# carte_moteurs_robotech.net
KiCad netlist of a schematic drawn in EAGLE
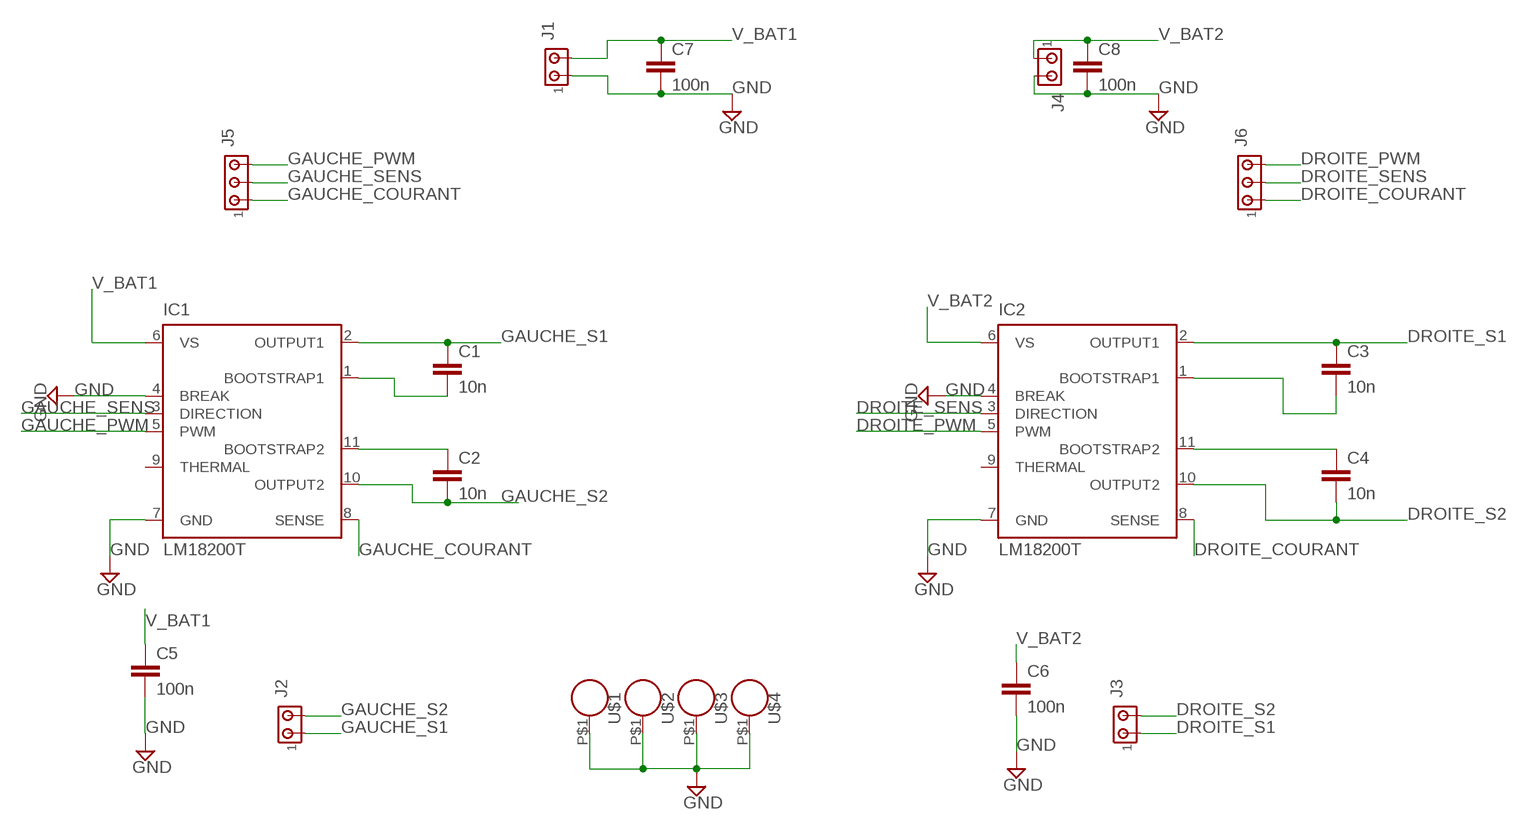
[diagram p0: schematic, sheet 1]

(export (version "E")
  (design (tool "Eeschema 10.0.6"))
  (components
    (comp (ref "C1")
      (value "10n")
      (footprint "eagle-import:C7.5B3")
      (libsource (lib "eagle-import") (part "C7.5/3"))
    )
    (comp (ref "C2")
      (value "10n")
      (footprint "eagle-import:C7.5B3")
      (libsource (lib "eagle-import") (part "C7.5/3"))
    )
    (comp (ref "C3")
      (value "10n")
      (footprint "eagle-import:C7.5B3")
      (libsource (lib "eagle-import") (part "C7.5/3"))
    )
    (comp (ref "C4")
      (value "10n")
      (footprint "eagle-import:C7.5B3")
      (libsource (lib "eagle-import") (part "C7.5/3"))
    )
    (comp (ref "C5")
      (value "100n")
      (footprint "eagle-import:C7.5B3")
      (libsource (lib "eagle-import") (part "C7.5/3"))
    )
    (comp (ref "C6")
      (value "100n")
      (footprint "eagle-import:C7.5B3")
      (libsource (lib "eagle-import") (part "C7.5/3"))
    )
    (comp (ref "C7")
      (value "100n")
      (footprint "eagle-import:C7.5B3")
      (libsource (lib "eagle-import") (part "C7.5/3"))
    )
    (comp (ref "C8")
      (value "100n")
      (footprint "eagle-import:C7.5B3")
      (libsource (lib "eagle-import") (part "C7.5/3"))
    )
    (comp (ref "IC1")
      (value "LM18200T")
      (footprint "eagle-import:TO-220-11")
      (libsource (lib "eagle-import") (part "LM18200T"))
    )
    (comp (ref "IC2")
      (value "LM18200T")
      (footprint "eagle-import:TO-220-11")
      (libsource (lib "eagle-import") (part "LM18200T"))
    )
    (comp (ref "J1")
      (value "MTA02-156")
      (footprint "eagle-import:1X2MTA")
      (libsource (lib "eagle-import") (part "MTA02-156"))
    )
    (comp (ref "J2")
      (value "MTA02-156")
      (footprint "eagle-import:1X2MTA")
      (libsource (lib "eagle-import") (part "MTA02-156"))
    )
    (comp (ref "J3")
      (value "MTA02-156")
      (footprint "eagle-import:1X2MTA")
      (libsource (lib "eagle-import") (part "MTA02-156"))
    )
    (comp (ref "J4")
      (value "MTA02-156")
      (footprint "eagle-import:1X2MTA")
      (libsource (lib "eagle-import") (part "MTA02-156"))
    )
    (comp (ref "J5")
      (value "MTA03-156")
      (footprint "eagle-import:1X3MTA")
      (libsource (lib "eagle-import") (part "MTA03-156"))
    )
    (comp (ref "J6")
      (value "MTA03-156")
      (footprint "eagle-import:1X3MTA")
      (libsource (lib "eagle-import") (part "MTA03-156"))
    )
    (comp (ref "U$1")
      (value "DRILL3META")
      (footprint "eagle-import:DRILL3ME")
      (libsource (lib "eagle-import") (part "DRILL3META"))
    )
    (comp (ref "U$2")
      (value "DRILL3META")
      (footprint "eagle-import:DRILL3ME")
      (libsource (lib "eagle-import") (part "DRILL3META"))
    )
    (comp (ref "U$3")
      (value "DRILL3META")
      (footprint "eagle-import:DRILL3ME")
      (libsource (lib "eagle-import") (part "DRILL3META"))
    )
    (comp (ref "U$4")
      (value "DRILL3META")
      (footprint "eagle-import:DRILL3ME")
      (libsource (lib "eagle-import") (part "DRILL3META"))
    )
  )
  (nets
    (net (code "1") (name "/DROITE_COURANT") (class "Default")
      (node (ref "IC2") (pin "8") (pinfunction "SENSE_8") (pintype "output"))
      (node (ref "J6") (pin "1") (pinfunction "1_1") (pintype "passive"))
    )
    (net (code "2") (name "/DROITE_PWM") (class "Default")
      (node (ref "IC2") (pin "5") (pinfunction "PWM_5") (pintype "input"))
      (node (ref "J6") (pin "3") (pinfunction "3_3") (pintype "passive"))
    )
    (net (code "3") (name "/DROITE_S1") (class "Default")
      (node (ref "C3") (pin "1") (pinfunction "1_1") (pintype "passive"))
      (node (ref "IC2") (pin "2") (pinfunction "OUTPUT1_2") (pintype "output"))
      (node (ref "J3") (pin "1") (pinfunction "1_1") (pintype "passive"))
    )
    (net (code "4") (name "/DROITE_S2") (class "Default")
      (node (ref "C4") (pin "2") (pinfunction "2_2") (pintype "passive"))
      (node (ref "IC2") (pin "10") (pinfunction "OUTPUT2_10") (pintype "output"))
      (node (ref "J3") (pin "2") (pinfunction "2_2") (pintype "passive"))
    )
    (net (code "5") (name "/DROITE_SENS") (class "Default")
      (node (ref "IC2") (pin "3") (pinfunction "DIRECTION_3") (pintype "input"))
      (node (ref "J6") (pin "2") (pinfunction "2_2") (pintype "passive"))
    )
    (net (code "6") (name "/GAUCHE_COURANT") (class "Default")
      (node (ref "IC1") (pin "8") (pinfunction "SENSE_8") (pintype "output"))
      (node (ref "J5") (pin "1") (pinfunction "1_1") (pintype "passive"))
    )
    (net (code "7") (name "/GAUCHE_PWM") (class "Default")
      (node (ref "IC1") (pin "5") (pinfunction "PWM_5") (pintype "input"))
      (node (ref "J5") (pin "3") (pinfunction "3_3") (pintype "passive"))
    )
    (net (code "8") (name "/GAUCHE_S1") (class "Default")
      (node (ref "C1") (pin "1") (pinfunction "1_1") (pintype "passive"))
      (node (ref "IC1") (pin "2") (pinfunction "OUTPUT1_2") (pintype "output"))
      (node (ref "J2") (pin "1") (pinfunction "1_1") (pintype "passive"))
    )
    (net (code "9") (name "/GAUCHE_S2") (class "Default")
      (node (ref "C2") (pin "2") (pinfunction "2_2") (pintype "passive"))
      (node (ref "IC1") (pin "10") (pinfunction "OUTPUT2_10") (pintype "output"))
      (node (ref "J2") (pin "2") (pinfunction "2_2") (pintype "passive"))
    )
    (net (code "10") (name "/GAUCHE_SENS") (class "Default")
      (node (ref "IC1") (pin "3") (pinfunction "DIRECTION_3") (pintype "input"))
      (node (ref "J5") (pin "2") (pinfunction "2_2") (pintype "passive"))
    )
    (net (code "11") (name "/V_BAT1") (class "Default")
      (node (ref "C5") (pin "1") (pinfunction "1_1") (pintype "passive"))
      (node (ref "C7") (pin "1") (pinfunction "1_1") (pintype "passive"))
      (node (ref "IC1") (pin "6") (pinfunction "VS_6") (pintype "power_in"))
      (node (ref "J1") (pin "2") (pinfunction "2_2") (pintype "passive"))
    )
    (net (code "12") (name "/V_BAT2") (class "Default")
      (node (ref "C6") (pin "1") (pinfunction "1_1") (pintype "passive"))
      (node (ref "C8") (pin "1") (pinfunction "1_1") (pintype "passive"))
      (node (ref "IC2") (pin "6") (pinfunction "VS_6") (pintype "power_in"))
      (node (ref "J4") (pin "1") (pinfunction "1_1") (pintype "passive"))
    )
    (net (code "13") (name "GND") (class "Default")
      (node (ref "C5") (pin "2") (pinfunction "2_2") (pintype "passive"))
      (node (ref "C6") (pin "2") (pinfunction "2_2") (pintype "passive"))
      (node (ref "C7") (pin "2") (pinfunction "2_2") (pintype "passive"))
      (node (ref "C8") (pin "2") (pinfunction "2_2") (pintype "passive"))
      (node (ref "IC1") (pin "4") (pinfunction "BREAK_4") (pintype "input"))
      (node (ref "IC1") (pin "7") (pinfunction "GND_7") (pintype "power_in"))
      (node (ref "IC2") (pin "4") (pinfunction "BREAK_4") (pintype "input"))
      (node (ref "IC2") (pin "7") (pinfunction "GND_7") (pintype "power_in"))
      (node (ref "J1") (pin "1") (pinfunction "1_1") (pintype "passive"))
      (node (ref "J4") (pin "2") (pinfunction "2_2") (pintype "passive"))
      (node (ref "U$1") (pin "P$1") (pinfunction "P_P$1") (pintype "bidirectional"))
      (node (ref "U$2") (pin "P$1") (pinfunction "P_P$1") (pintype "bidirectional"))
      (node (ref "U$3") (pin "P$1") (pinfunction "P_P$1") (pintype "bidirectional"))
      (node (ref "U$4") (pin "P$1") (pinfunction "P_P$1") (pintype "bidirectional"))
    )
    (net (code "14") (name "Net-(IC1-BOOTSTRAP1)") (class "Default")
      (node (ref "C1") (pin "2") (pinfunction "2_2") (pintype "passive"))
      (node (ref "IC1") (pin "1") (pinfunction "BOOTSTRAP1_1") (pintype "input"))
    )
    (net (code "15") (name "Net-(IC1-BOOTSTRAP2)") (class "Default")
      (node (ref "C2") (pin "1") (pinfunction "1_1") (pintype "passive"))
      (node (ref "IC1") (pin "11") (pinfunction "BOOTSTRAP2_11") (pintype "input"))
    )
    (net (code "16") (name "Net-(IC2-BOOTSTRAP1)") (class "Default")
      (node (ref "C3") (pin "2") (pinfunction "2_2") (pintype "passive"))
      (node (ref "IC2") (pin "1") (pinfunction "BOOTSTRAP1_1") (pintype "input"))
    )
    (net (code "17") (name "Net-(IC2-BOOTSTRAP2)") (class "Default")
      (node (ref "C4") (pin "1") (pinfunction "1_1") (pintype "passive"))
      (node (ref "IC2") (pin "11") (pinfunction "BOOTSTRAP2_11") (pintype "input"))
    )
    (net (code "18") (name "unconnected-(IC1-THERMAL-Pad9)") (class "Default")
      (node (ref "IC1") (pin "9") (pinfunction "THERMAL_9") (pintype "output"))
    )
    (net (code "19") (name "unconnected-(IC2-THERMAL-Pad9)") (class "Default")
      (node (ref "IC2") (pin "9") (pinfunction "THERMAL_9") (pintype "output"))
    )
  )
)
